# CirkPic.net
KiCad netlist of a schematic drawn in Altium Designer
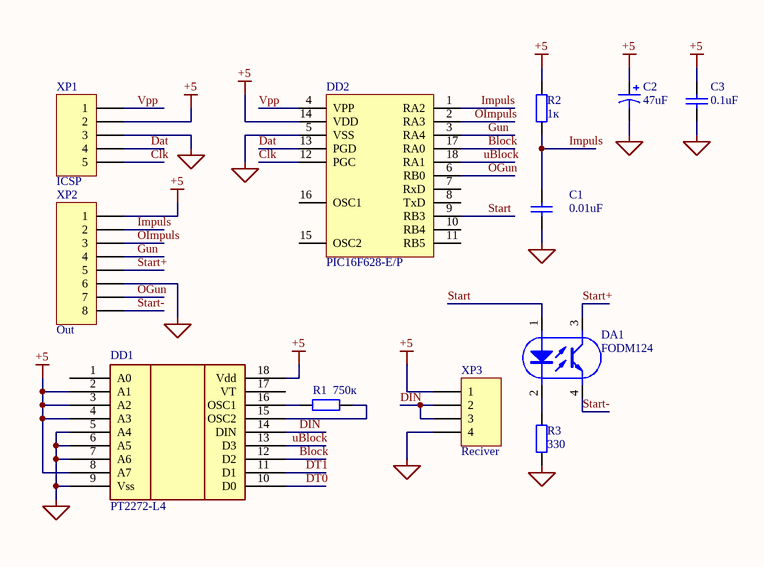
[diagram p0: CirkPic.SchDoc]

(export (version "E")
  (design (tool "Eeschema 10.0.6"))
  (components
    (comp (ref "C1")
      (value "0.01uF")
      (footprint "CAPC2012N")
      (description "Capacitor")
      (fields (field (name "Comment") "Cap") (field (name "PUBLISHER") "Altium Limited"))
      (libsource (lib "Miscellaneous Devices") (part "Cap"))
    )
    (comp (ref "C2")
      (value "47uF")
      (footprint "TC3528-1411")
      (description "Polarized Capacitor (Radial)")
      (fields (field (name "Comment") "Cap Pol1") (field (name "PUBLISHER") "Altium Limited"))
      (libsource (lib "Miscellaneous Devices") (part "Cap Pol1"))
    )
    (comp (ref "C3")
      (value "0.1uF")
      (footprint "CAPC2012N")
      (description "Capacitor")
      (fields (field (name "Comment") "Cap") (field (name "PUBLISHER") "Altium Limited"))
      (libsource (lib "Miscellaneous Devices") (part "Cap"))
    )
    (comp (ref "DA1")
      (value "FODM124")
      (footprint "DIP-4")
      (description "5 Pin Mini Flat Pack Optocoupler")
      (fields (field (name "Comment") "Optoisolator2") (field (name "PUBLISHER") "Altium Limited"))
      (libsource (lib "Cirk_3") (part "Optoisolator2"))
    )
    (comp (ref "DD1") (value "PT2272-L4") (footprint "DIP-18") (libsource (lib "Cirk") (part "PT2272")))
    (comp (ref "DD2")
      (value "PIC16F628-E/P")
      (footprint "DIP-18")
      (fields (field (name "PUBLISHER") "Altium Limited"))
      (libsource (lib "Cirk_1") (part "PIC16F628A-E/P"))
    )
    (comp (ref "R1")
      (value "750к")
      (footprint "RESC2012N")
      (description "Resistor")
      (fields (field (name "Comment") "Res2") (field (name "PUBLISHER") "Altium Limited"))
      (libsource (lib "Miscellaneous Devices") (part "Res2"))
    )
    (comp (ref "R2")
      (value "1к")
      (footprint "RESC2012N")
      (description "Resistor")
      (fields (field (name "Comment") "Res2") (field (name "PUBLISHER") "Altium Limited"))
      (libsource (lib "") (part "Res2_1"))
    )
    (comp (ref "R3")
      (value "330")
      (footprint "RESC3216N")
      (description "Resistor")
      (fields (field (name "Comment") "Res2") (field (name "PUBLISHER") "Altium Limited"))
      (libsource (lib "") (part "Res2_2"))
    )
    (comp (ref "XP1")
      (value "ICSP")
      (footprint "HDR1X5")
      (description "Header, 5-Pin")
      (fields (field (name "PUBLISHER") "Altium Limited"))
      (libsource (lib "Miscellaneous Connectors") (part "Header 5"))
    )
    (comp (ref "XP2")
      (value "Out")
      (footprint "HDR1X8")
      (description "Header, 8-Pin")
      (fields (field (name "PUBLISHER") "Altium Limited"))
      (libsource (lib "Miscellaneous Connectors") (part "Header 8"))
    )
    (comp (ref "XP3")
      (value "Reciver")
      (footprint "HDR1X4")
      (description "Header, 4-Pin")
      (fields (field (name "PUBLISHER") "Altium Limited"))
      (libsource (lib "Miscellaneous Connectors") (part "Header 4"))
    )
  )
  (nets
    (net (code "1") (name "+5") (class "Default")
      (node (ref "C2") (pin "1") (pinfunction "1_1") (pintype "passive"))
      (node (ref "C3") (pin "2") (pinfunction "2_2") (pintype "passive"))
      (node (ref "DD1") (pin "18") (pinfunction "Vdd_18") (pintype "passive"))
      (node (ref "DD1") (pin "2") (pinfunction "A1_2") (pintype "passive"))
      (node (ref "DD1") (pin "3") (pinfunction "A2_3") (pintype "passive"))
      (node (ref "DD1") (pin "4") (pinfunction "A3_4") (pintype "passive"))
      (node (ref "DD1") (pin "8") (pinfunction "A7_8") (pintype "passive"))
      (node (ref "DD2") (pin "14") (pinfunction "VDD_14") (pintype "power_in"))
      (node (ref "R2") (pin "2") (pinfunction "2_2") (pintype "passive"))
      (node (ref "XP1") (pin "2") (pinfunction "2_2") (pintype "passive"))
      (node (ref "XP2") (pin "1") (pinfunction "1_1") (pintype "passive"))
      (node (ref "XP3") (pin "1") (pinfunction "1_1") (pintype "passive"))
    )
    (net (code "2") (name "/Block") (class "Default")
      (node (ref "DD1") (pin "12") (pinfunction "D2_12") (pintype "passive"))
      (node (ref "DD2") (pin "17") (pinfunction "RA0_17") (pintype "passive"))
    )
    (net (code "3") (name "/Clk") (class "Default")
      (node (ref "DD2") (pin "12") (pinfunction "PGC_12") (pintype "passive"))
      (node (ref "XP1") (pin "5") (pinfunction "5_5") (pintype "passive"))
    )
    (net (code "4") (name "/DIN") (class "Default")
      (node (ref "DD1") (pin "14") (pinfunction "DIN_14") (pintype "passive"))
      (node (ref "XP3") (pin "2") (pinfunction "2_2") (pintype "passive"))
      (node (ref "XP3") (pin "3") (pinfunction "3_3") (pintype "passive"))
    )
    (net (code "5") (name "/DT0") (class "Default")
      (node (ref "DD1") (pin "10") (pinfunction "D0_10") (pintype "passive"))
    )
    (net (code "6") (name "/DT1") (class "Default")
      (node (ref "DD1") (pin "11") (pinfunction "D1_11") (pintype "passive"))
    )
    (net (code "7") (name "/Dat") (class "Default")
      (node (ref "DD2") (pin "13") (pinfunction "PGD_13") (pintype "passive"))
      (node (ref "XP1") (pin "4") (pinfunction "4_4") (pintype "passive"))
    )
    (net (code "8") (name "/Gun") (class "Default")
      (node (ref "DD2") (pin "3") (pinfunction "RA4_3") (pintype "passive"))
      (node (ref "XP2") (pin "4") (pinfunction "4_4") (pintype "passive"))
    )
    (net (code "9") (name "/Impuls") (class "Default")
      (node (ref "C1") (pin "2") (pinfunction "2_2") (pintype "passive"))
      (node (ref "DD2") (pin "1") (pinfunction "RA2_1") (pintype "passive"))
      (node (ref "R2") (pin "1") (pinfunction "1_1") (pintype "passive"))
      (node (ref "XP2") (pin "2") (pinfunction "2_2") (pintype "passive"))
    )
    (net (code "10") (name "/OGun") (class "Default")
      (node (ref "DD2") (pin "6") (pinfunction "RB0_6") (pintype "passive"))
      (node (ref "XP2") (pin "7") (pinfunction "7_7") (pintype "passive"))
    )
    (net (code "11") (name "/OImpuls") (class "Default")
      (node (ref "DD2") (pin "2") (pinfunction "RA3_2") (pintype "passive"))
      (node (ref "XP2") (pin "3") (pinfunction "3_3") (pintype "passive"))
    )
    (net (code "12") (name "/Start") (class "Default")
      (node (ref "DA1") (pin "1") (pinfunction "A_1") (pintype "passive"))
      (node (ref "DD2") (pin "9") (pinfunction "RB3_9") (pintype "passive"))
    )
    (net (code "13") (name "/Start+") (class "Default")
      (node (ref "DA1") (pin "3") (pinfunction "C_3") (pintype "passive"))
      (node (ref "XP2") (pin "5") (pinfunction "5_5") (pintype "passive"))
    )
    (net (code "14") (name "/Start-") (class "Default")
      (node (ref "DA1") (pin "4") (pinfunction "E_4") (pintype "passive"))
      (node (ref "XP2") (pin "8") (pinfunction "8_8") (pintype "passive"))
    )
    (net (code "15") (name "/Vpp") (class "Default")
      (node (ref "DD2") (pin "4") (pinfunction "VPP_4") (pintype "passive"))
      (node (ref "XP1") (pin "1") (pinfunction "1_1") (pintype "passive"))
    )
    (net (code "16") (name "/uBlock") (class "Default")
      (node (ref "DD1") (pin "13") (pinfunction "D3_13") (pintype "passive"))
      (node (ref "DD2") (pin "18") (pinfunction "RA1_18") (pintype "passive"))
    )
    (net (code "17") (name "GND") (class "Default")
      (node (ref "C1") (pin "1") (pinfunction "1_1") (pintype "passive"))
      (node (ref "C2") (pin "2") (pinfunction "2_2") (pintype "passive"))
      (node (ref "C3") (pin "1") (pinfunction "1_1") (pintype "passive"))
      (node (ref "DD1") (pin "5") (pinfunction "A4_5") (pintype "passive"))
      (node (ref "DD1") (pin "6") (pinfunction "A5_6") (pintype "passive"))
      (node (ref "DD1") (pin "7") (pinfunction "A6_7") (pintype "passive"))
      (node (ref "DD1") (pin "9") (pinfunction "Vss_9") (pintype "passive"))
      (node (ref "DD2") (pin "5") (pinfunction "VSS_5") (pintype "power_in"))
      (node (ref "R3") (pin "2") (pinfunction "2_2") (pintype "passive"))
      (node (ref "XP1") (pin "3") (pinfunction "3_3") (pintype "passive"))
      (node (ref "XP2") (pin "6") (pinfunction "6_6") (pintype "passive"))
      (node (ref "XP3") (pin "4") (pinfunction "4_4") (pintype "passive"))
    )
    (net (code "18") (name "Net-(DA1-K)") (class "Default")
      (node (ref "DA1") (pin "2") (pinfunction "K_2") (pintype "passive"))
      (node (ref "R3") (pin "1") (pinfunction "1_1") (pintype "passive"))
    )
    (net (code "19") (name "Net-(DD1-OSC1)") (class "Default")
      (node (ref "DD1") (pin "16") (pinfunction "OSC1_16") (pintype "passive"))
      (node (ref "R1") (pin "1") (pinfunction "1_1") (pintype "passive"))
    )
    (net (code "20") (name "Net-(DD1-OSC2)") (class "Default")
      (node (ref "DD1") (pin "15") (pinfunction "OSC2_15") (pintype "passive"))
      (node (ref "R1") (pin "2") (pinfunction "2_2") (pintype "passive"))
    )
    (net (code "21") (name "unconnected-(DD1-A0-Pad1)") (class "Default")
      (node (ref "DD1") (pin "1") (pinfunction "A0_1") (pintype "passive"))
    )
    (net (code "22") (name "unconnected-(DD1-VT-Pad17)") (class "Default")
      (node (ref "DD1") (pin "17") (pinfunction "VT_17") (pintype "passive"))
    )
    (net (code "23") (name "unconnected-(DD2-OSC1-Pad16)") (class "Default")
      (node (ref "DD2") (pin "16") (pinfunction "OSC1_16") (pintype "passive"))
    )
    (net (code "24") (name "unconnected-(DD2-OSC2-Pad15)") (class "Default")
      (node (ref "DD2") (pin "15") (pinfunction "OSC2_15") (pintype "passive"))
    )
    (net (code "25") (name "unconnected-(DD2-RB4-Pad10)") (class "Default")
      (node (ref "DD2") (pin "10") (pinfunction "RB4_10") (pintype "passive"))
    )
    (net (code "26") (name "unconnected-(DD2-RB5-Pad11)") (class "Default")
      (node (ref "DD2") (pin "11") (pinfunction "RB5_11") (pintype "passive"))
    )
    (net (code "27") (name "unconnected-(DD2-RxD-Pad7)") (class "Default")
      (node (ref "DD2") (pin "7") (pinfunction "RxD_7") (pintype "passive"))
    )
    (net (code "28") (name "unconnected-(DD2-TxD-Pad8)") (class "Default")
      (node (ref "DD2") (pin "8") (pinfunction "TxD_8") (pintype "passive"))
    )
  )
)
